# StairLightController.net
KiCad netlist of a schematic drawn in EAGLE
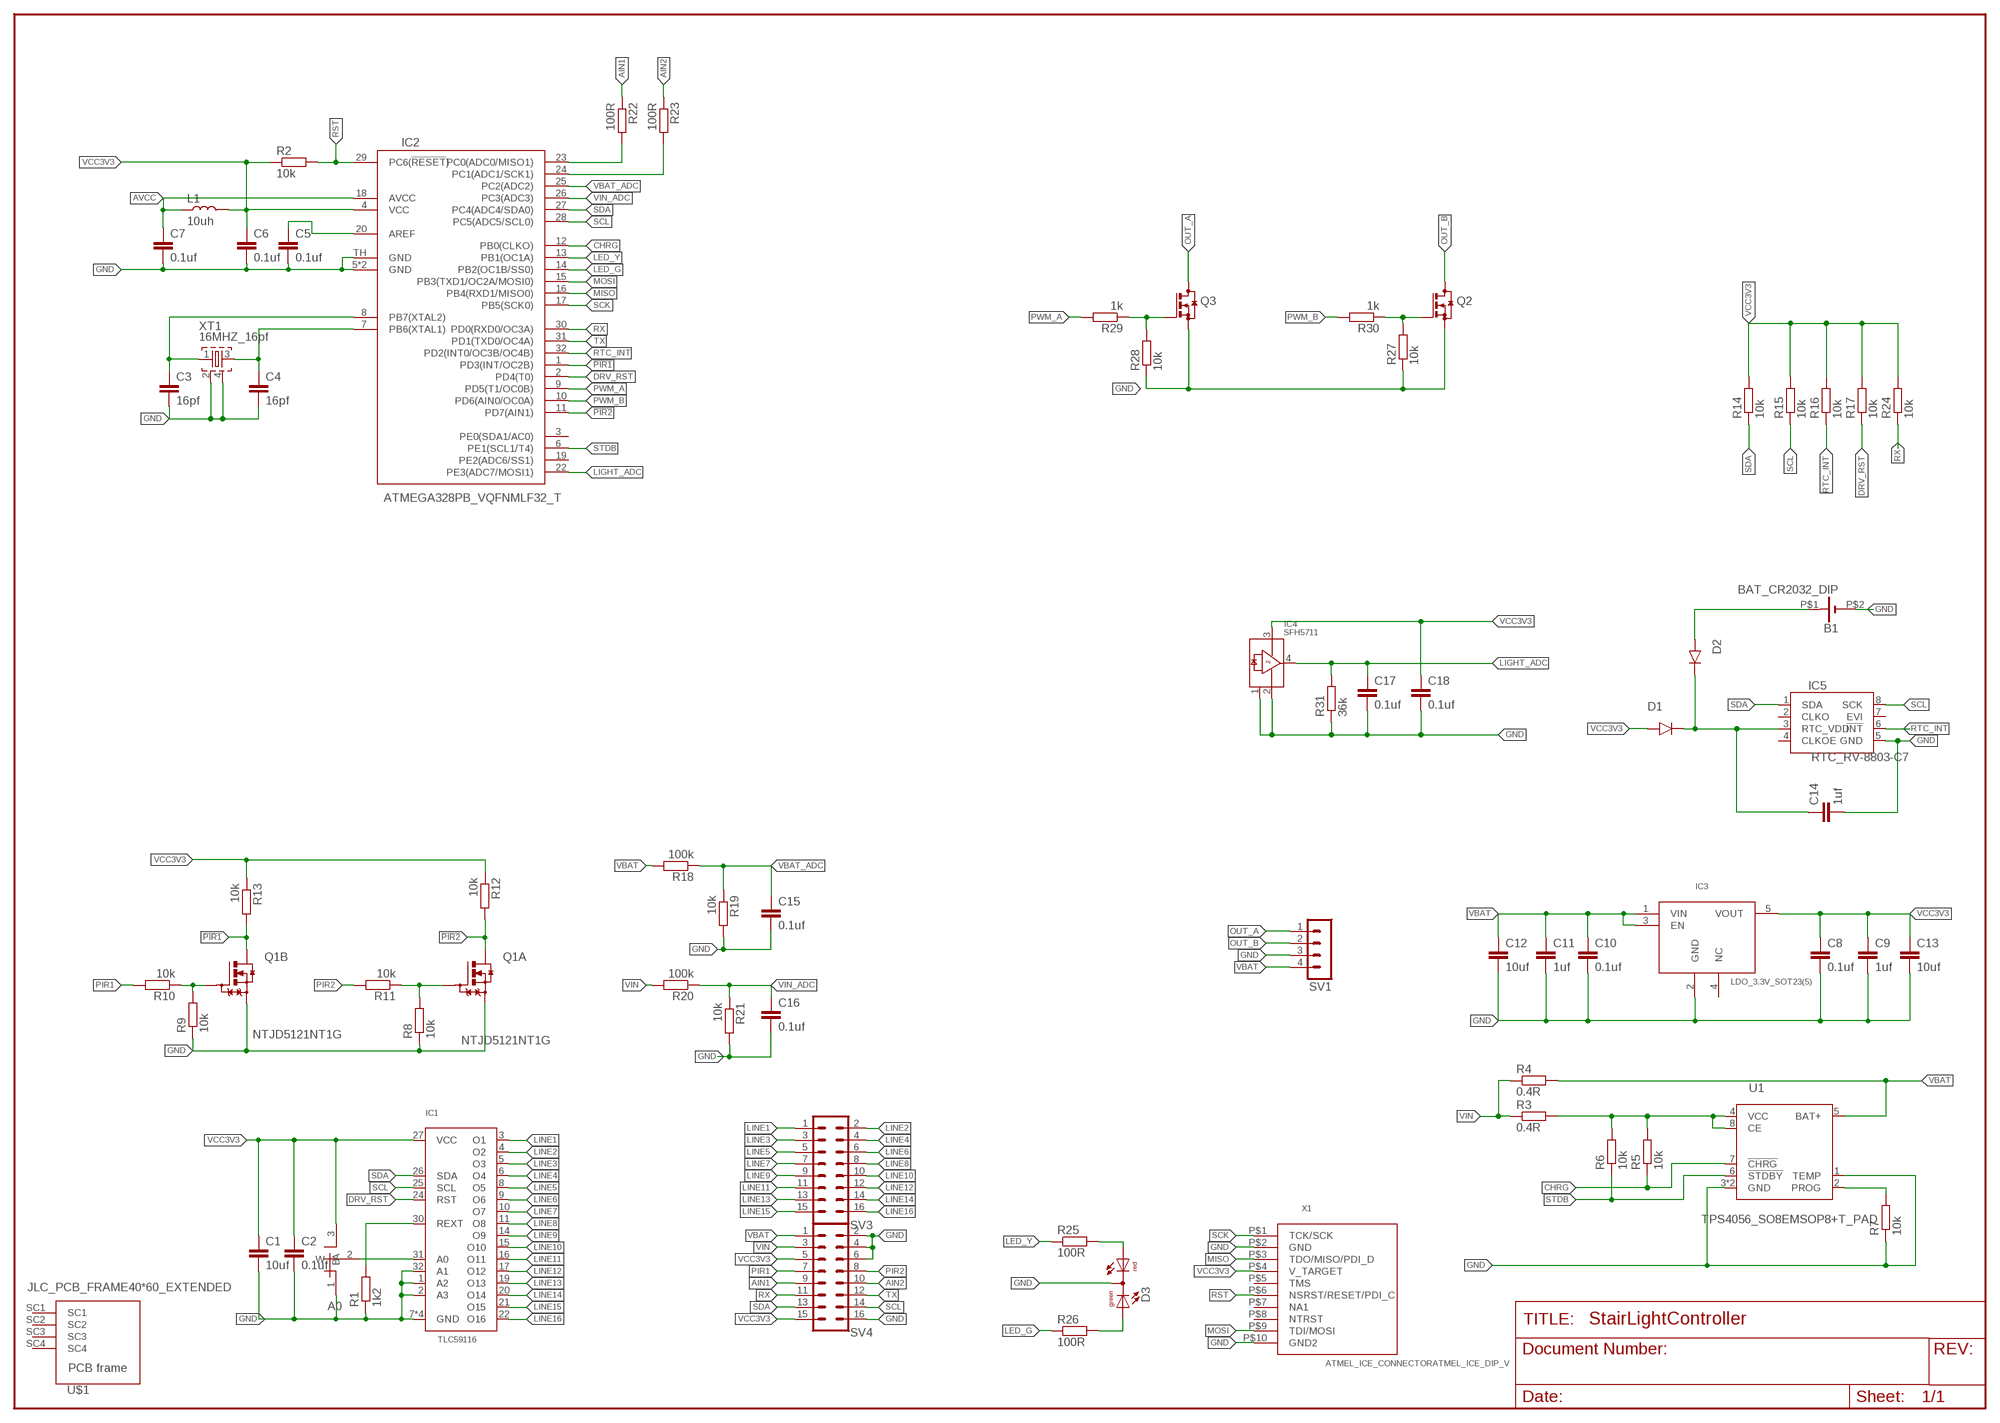
[diagram p0: schematic, sheet 1]

(export (version "E")
  (design (tool "Eeschema 10.0.6"))
  (components
    (comp (ref "A0")
      (value "SMD_SWITCH_JUMPER")
      (footprint "eagle-import:0603_JUMP")
      (libsource (lib "eagle-import") (part "SMD_SWITCH_JUMPER"))
    )
    (comp (ref "B1")
      (value "BAT_CR2032_DIP")
      (footprint "eagle-import:CR2032_DIP")
      (libsource (lib "eagle-import") (part "BAT_CR2032_DIP"))
    )
    (comp (ref "C1")
      (value "10uf")
      (footprint "eagle-import:0603")
      (libsource (lib "eagle-import") (part "SMD_C0603"))
    )
    (comp (ref "C2")
      (value "0.1uf")
      (footprint "eagle-import:0603")
      (libsource (lib "eagle-import") (part "SMD_C0603"))
    )
    (comp (ref "C3")
      (value "16pf")
      (footprint "eagle-import:0603")
      (libsource (lib "eagle-import") (part "SMD_C0603"))
    )
    (comp (ref "C4")
      (value "16pf")
      (footprint "eagle-import:0603")
      (libsource (lib "eagle-import") (part "SMD_C0603"))
    )
    (comp (ref "C5")
      (value "0.1uf")
      (footprint "eagle-import:0603")
      (libsource (lib "eagle-import") (part "SMD_C0603"))
    )
    (comp (ref "C6")
      (value "0.1uf")
      (footprint "eagle-import:0603")
      (libsource (lib "eagle-import") (part "SMD_C0603"))
    )
    (comp (ref "C7")
      (value "0.1uf")
      (footprint "eagle-import:0603")
      (libsource (lib "eagle-import") (part "SMD_C0603"))
    )
    (comp (ref "C8")
      (value "0.1uf")
      (footprint "eagle-import:0603")
      (libsource (lib "eagle-import") (part "SMD_C0603"))
    )
    (comp (ref "C9")
      (value "1uf")
      (footprint "eagle-import:0603")
      (libsource (lib "eagle-import") (part "SMD_C0603"))
    )
    (comp (ref "C10")
      (value "0.1uf")
      (footprint "eagle-import:0603")
      (libsource (lib "eagle-import") (part "SMD_C0603"))
    )
    (comp (ref "C11")
      (value "1uf")
      (footprint "eagle-import:0603")
      (libsource (lib "eagle-import") (part "SMD_C0603"))
    )
    (comp (ref "C12")
      (value "10uf")
      (footprint "eagle-import:1206")
      (libsource (lib "eagle-import") (part "SMD_C1206"))
    )
    (comp (ref "C13")
      (value "10uf")
      (footprint "eagle-import:1206")
      (libsource (lib "eagle-import") (part "SMD_C1206"))
    )
    (comp (ref "C14")
      (value "1uf")
      (footprint "eagle-import:0603")
      (libsource (lib "eagle-import") (part "SMD_C0603"))
    )
    (comp (ref "C15")
      (value "0.1uf")
      (footprint "eagle-import:0603")
      (libsource (lib "eagle-import") (part "SMD_C0603"))
    )
    (comp (ref "C16")
      (value "0.1uf")
      (footprint "eagle-import:0603")
      (libsource (lib "eagle-import") (part "SMD_C0603"))
    )
    (comp (ref "C17")
      (value "0.1uf")
      (footprint "eagle-import:0603")
      (libsource (lib "eagle-import") (part "SMD_C0603"))
    )
    (comp (ref "C18")
      (value "0.1uf")
      (footprint "eagle-import:0603")
      (libsource (lib "eagle-import") (part "SMD_C0603"))
    )
    (comp (ref "D1")
      (value "L1N4148WT1GSOD123_GALILE0_SMALL")
      (footprint "eagle-import:SOD-123_MINI-SMA")
      (libsource (lib "eagle-import") (part "L1N4148WT1GSOD123_GALILE0_SMALL"))
    )
    (comp (ref "D2")
      (value "L1N4148WT1GSOD123_GALILE0_SMALL")
      (footprint "eagle-import:SOD-123_MINI-SMA")
      (libsource (lib "eagle-import") (part "L1N4148WT1GSOD123_GALILE0_SMALL"))
    )
    (comp (ref "D3")
      (value "DUOLED5MM")
      (footprint "eagle-import:DUOLED5MM")
      (libsource (lib "eagle-import") (part "DUOLED5MM"))
    )
    (comp (ref "IC1")
      (value "TLC59116")
      (footprint "eagle-import:MLF32-TH")
      (libsource (lib "eagle-import") (part "TLC59116"))
    )
    (comp (ref "IC2")
      (value "ATMEGA328PB_VQFNMLF32_T")
      (footprint "eagle-import:MLF32-TH")
      (libsource (lib "eagle-import") (part "ATMEGA328PB_VQFNMLF32_T"))
    )
    (comp (ref "IC3")
      (value "LDO_3.3V_SOT23(5)")
      (footprint "eagle-import:SOT-23(5)")
      (libsource (lib "eagle-import") (part "LDO_3.3V_SOT23(5)"))
    )
    (comp (ref "IC4")
      (value "SFH5711")
      (footprint "eagle-import:SFH5711")
      (fields (field (name "MF") "OSRAM Opto"))
      (libsource (lib "eagle-import") (part "SFH5711"))
    )
    (comp (ref "IC5")
      (value "RTC_RV-8803-C7")
      (footprint "eagle-import:C7_RTC")
      (libsource (lib "eagle-import") (part "RTC_RV-8803-C7"))
    )
    (comp (ref "L1")
      (value "10uh")
      (footprint "eagle-import:0603")
      (libsource (lib "eagle-import") (part "SMD_L0603"))
    )
    (comp (ref "Q1")
      (value "NTJD5121NT1G")
      (footprint "eagle-import:SOT363")
      (fields (field (name "MF") "ON SEMICONDUCTOR"))
      (libsource (lib "eagle-import") (part "NTJD5121NT1G"))
    )
    (comp (ref "Q2")
      (value "BSS123SOT-23-3")
      (footprint "eagle-import:SOT-23(3)")
      (libsource (lib "eagle-import") (part "BSS123SOT-23-3"))
    )
    (comp (ref "Q3")
      (value "BSS123SOT-23-3")
      (footprint "eagle-import:SOT-23(3)")
      (libsource (lib "eagle-import") (part "BSS123SOT-23-3"))
    )
    (comp (ref "R1")
      (value "1k2")
      (footprint "eagle-import:0603")
      (libsource (lib "eagle-import") (part "SMD_R0603"))
    )
    (comp (ref "R2")
      (value "10k")
      (footprint "eagle-import:0603")
      (libsource (lib "eagle-import") (part "SMD_R0603"))
    )
    (comp (ref "R3")
      (value "0.4R")
      (footprint "eagle-import:1206")
      (libsource (lib "eagle-import") (part "SMD_R1206"))
    )
    (comp (ref "R4")
      (value "0.4R")
      (footprint "eagle-import:1206")
      (libsource (lib "eagle-import") (part "SMD_R1206"))
    )
    (comp (ref "R5")
      (value "10k")
      (footprint "eagle-import:0603")
      (libsource (lib "eagle-import") (part "SMD_R0603"))
    )
    (comp (ref "R6")
      (value "10k")
      (footprint "eagle-import:0603")
      (libsource (lib "eagle-import") (part "SMD_R0603"))
    )
    (comp (ref "R7")
      (value "10k")
      (footprint "eagle-import:0603")
      (libsource (lib "eagle-import") (part "SMD_R0603"))
    )
    (comp (ref "R8")
      (value "10k")
      (footprint "eagle-import:0603")
      (libsource (lib "eagle-import") (part "SMD_R0603"))
    )
    (comp (ref "R9")
      (value "10k")
      (footprint "eagle-import:0603")
      (libsource (lib "eagle-import") (part "SMD_R0603"))
    )
    (comp (ref "R10")
      (value "10k")
      (footprint "eagle-import:0603")
      (libsource (lib "eagle-import") (part "SMD_R0603"))
    )
    (comp (ref "R11")
      (value "10k")
      (footprint "eagle-import:0603")
      (libsource (lib "eagle-import") (part "SMD_R0603"))
    )
    (comp (ref "R12")
      (value "10k")
      (footprint "eagle-import:0603")
      (libsource (lib "eagle-import") (part "SMD_R0603"))
    )
    (comp (ref "R13")
      (value "10k")
      (footprint "eagle-import:0603")
      (libsource (lib "eagle-import") (part "SMD_R0603"))
    )
    (comp (ref "R14")
      (value "10k")
      (footprint "eagle-import:0603")
      (libsource (lib "eagle-import") (part "SMD_R0603"))
    )
    (comp (ref "R15")
      (value "10k")
      (footprint "eagle-import:0603")
      (libsource (lib "eagle-import") (part "SMD_R0603"))
    )
    (comp (ref "R16")
      (value "10k")
      (footprint "eagle-import:0603")
      (libsource (lib "eagle-import") (part "SMD_R0603"))
    )
    (comp (ref "R17")
      (value "10k")
      (footprint "eagle-import:0603")
      (libsource (lib "eagle-import") (part "SMD_R0603"))
    )
    (comp (ref "R18")
      (value "100k")
      (footprint "eagle-import:0603")
      (libsource (lib "eagle-import") (part "SMD_R0603"))
    )
    (comp (ref "R19")
      (value "10k")
      (footprint "eagle-import:0603")
      (libsource (lib "eagle-import") (part "SMD_R0603"))
    )
    (comp (ref "R20")
      (value "100k")
      (footprint "eagle-import:0603")
      (libsource (lib "eagle-import") (part "SMD_R0603"))
    )
    (comp (ref "R21")
      (value "10k")
      (footprint "eagle-import:0603")
      (libsource (lib "eagle-import") (part "SMD_R0603"))
    )
    (comp (ref "R22")
      (value "100R")
      (footprint "eagle-import:0603")
      (libsource (lib "eagle-import") (part "SMD_R0603"))
    )
    (comp (ref "R23")
      (value "100R")
      (footprint "eagle-import:0603")
      (libsource (lib "eagle-import") (part "SMD_R0603"))
    )
    (comp (ref "R24")
      (value "10k")
      (footprint "eagle-import:0603")
      (libsource (lib "eagle-import") (part "SMD_R0603"))
    )
    (comp (ref "R25")
      (value "100R")
      (footprint "eagle-import:0603")
      (libsource (lib "eagle-import") (part "SMD_R0603"))
    )
    (comp (ref "R26")
      (value "100R")
      (footprint "eagle-import:0603")
      (libsource (lib "eagle-import") (part "SMD_R0603"))
    )
    (comp (ref "R27")
      (value "10k")
      (footprint "eagle-import:0603")
      (libsource (lib "eagle-import") (part "SMD_R0603"))
    )
    (comp (ref "R28")
      (value "10k")
      (footprint "eagle-import:0603")
      (libsource (lib "eagle-import") (part "SMD_R0603"))
    )
    (comp (ref "R29")
      (value "1k")
      (footprint "eagle-import:0603")
      (libsource (lib "eagle-import") (part "SMD_R0603"))
    )
    (comp (ref "R30")
      (value "1k")
      (footprint "eagle-import:0603")
      (libsource (lib "eagle-import") (part "SMD_R0603"))
    )
    (comp (ref "R31")
      (value "36k")
      (footprint "eagle-import:0603")
      (libsource (lib "eagle-import") (part "SMD_R0603"))
    )
    (comp (ref "SV1")
      (value "MA04-1")
      (footprint "eagle-import:MA04-1")
      (libsource (lib "eagle-import") (part "MA04-1"))
    )
    (comp (ref "SV3")
      (value "MA08-2")
      (footprint "eagle-import:MA08-2")
      (libsource (lib "eagle-import") (part "MA08-2"))
    )
    (comp (ref "SV4")
      (value "MA08-2")
      (footprint "eagle-import:MA08-2")
      (libsource (lib "eagle-import") (part "MA08-2"))
    )
    (comp (ref "U$1")
      (value "JLC_PCB_FRAME40*60_EXTENDED")
      (footprint "eagle-import:40X60_SENSOR_UNIT_OPEN")
      (libsource (lib "eagle-import") (part "JLC_PCB_FRAME4060_EXTENDED"))
    )
    (comp (ref "U1")
      (value "TPS4056_SO8EMSOP8+T_PAD")
      (footprint "eagle-import:EMSOP8+TPAD")
      (libsource (lib "eagle-import") (part "TPS4056_SO8EMSOP8+T_PAD"))
    )
    (comp (ref "X1")
      (value "ATMEL_ICE_CONNECTORATMEL_ICE_DIP_V")
      (footprint "eagle-import:MINI10P_SPI_JTAG_PDI_DIP_V")
      (libsource (lib "eagle-import") (part "ATMEL_ICE_CONNECTORATMEL_ICE_DIP_V"))
    )
    (comp (ref "XT1")
      (value "16MHZ_16pf")
      (footprint "eagle-import:QUARTZ_3X3MM")
      (libsource (lib "eagle-import") (part "QUARTZ_ZQ"))
    )
  )
  (nets
    (net (code "1") (name "/~{PIR1}") (class "Default")
      (node (ref "IC2") (pin "1") (pinfunction "PD3(INT/OC2B)_1") (pintype "bidirectional"))
      (node (ref "Q1") (pin "3") (pinfunction "D_3") (pintype "passive"))
      (node (ref "R13") (pin "2") (pinfunction "2_2") (pintype "passive"))
    )
    (net (code "2") (name "/~{PIR2}") (class "Default")
      (node (ref "IC2") (pin "11") (pinfunction "PD7(AIN1)_11") (pintype "bidirectional"))
      (node (ref "Q1") (pin "6") (pinfunction "D_6") (pintype "passive"))
      (node (ref "R12") (pin "2") (pinfunction "2_2") (pintype "passive"))
    )
    (net (code "3") (name "AIN1") (class "Default")
      (node (ref "R22") (pin "1") (pinfunction "1_1") (pintype "passive"))
      (node (ref "SV4") (pin "9") (pinfunction "9_9") (pintype "passive"))
    )
    (net (code "4") (name "AIN2") (class "Default")
      (node (ref "R23") (pin "1") (pinfunction "1_1") (pintype "passive"))
      (node (ref "SV4") (pin "10") (pinfunction "10_10") (pintype "passive"))
    )
    (net (code "5") (name "AVCC") (class "Default")
      (node (ref "C7") (pin "1") (pinfunction "1_1") (pintype "passive"))
      (node (ref "IC2") (pin "18") (pinfunction "AVCC_18") (pintype "power_in"))
      (node (ref "L1") (pin "1") (pinfunction "1_1") (pintype "passive"))
    )
    (net (code "6") (name "CHRG") (class "Default")
      (node (ref "IC2") (pin "12") (pinfunction "PB0(CLKO)_12") (pintype "bidirectional"))
      (node (ref "R5") (pin "1") (pinfunction "1_1") (pintype "passive"))
      (node (ref "U1") (pin "7") (pinfunction "~{CHRG}_7") (pintype "bidirectional"))
    )
    (net (code "7") (name "DRV_RST") (class "Default")
      (node (ref "IC1") (pin "24") (pinfunction "RST_24") (pintype "bidirectional"))
      (node (ref "IC2") (pin "2") (pinfunction "PD4(T0)_2") (pintype "bidirectional"))
      (node (ref "R17") (pin "1") (pinfunction "1_1") (pintype "passive"))
    )
    (net (code "8") (name "GND") (class "Default")
      (node (ref "A0") (pin "1") (pinfunction "A_1") (pintype "bidirectional"))
      (node (ref "B1") (pin "P$2") (pinfunction "-_P$2") (pintype "passive"))
      (node (ref "C1") (pin "2") (pinfunction "2_2") (pintype "passive"))
      (node (ref "C10") (pin "2") (pinfunction "2_2") (pintype "passive"))
      (node (ref "C11") (pin "2") (pinfunction "2_2") (pintype "passive"))
      (node (ref "C12") (pin "2") (pinfunction "2_2") (pintype "passive"))
      (node (ref "C13") (pin "2") (pinfunction "2_2") (pintype "passive"))
      (node (ref "C14") (pin "2") (pinfunction "2_2") (pintype "passive"))
      (node (ref "C15") (pin "2") (pinfunction "2_2") (pintype "passive"))
      (node (ref "C16") (pin "2") (pinfunction "2_2") (pintype "passive"))
      (node (ref "C17") (pin "2") (pinfunction "2_2") (pintype "passive"))
      (node (ref "C18") (pin "2") (pinfunction "2_2") (pintype "passive"))
      (node (ref "C2") (pin "2") (pinfunction "2_2") (pintype "passive"))
      (node (ref "C3") (pin "2") (pinfunction "2_2") (pintype "passive"))
      (node (ref "C4") (pin "2") (pinfunction "2_2") (pintype "passive"))
      (node (ref "C5") (pin "2") (pinfunction "2_2") (pintype "passive"))
      (node (ref "C6") (pin "2") (pinfunction "2_2") (pintype "passive"))
      (node (ref "C7") (pin "2") (pinfunction "2_2") (pintype "passive"))
      (node (ref "C8") (pin "2") (pinfunction "2_2") (pintype "passive"))
      (node (ref "C9") (pin "2") (pinfunction "2_2") (pintype "passive"))
      (node (ref "D3") (pin "K") (pinfunction "C_K") (pintype "passive"))
      (node (ref "IC1") (pin "1") (pinfunction "A2_1") (pintype "bidirectional"))
      (node (ref "IC1") (pin "18") (pinfunction "GND_18") (pintype "bidirectional"))
      (node (ref "IC1") (pin "2") (pinfunction "A3_2") (pintype "bidirectional"))
      (node (ref "IC1") (pin "23") (pinfunction "GND_23") (pintype "bidirectional"))
      (node (ref "IC1") (pin "32") (pinfunction "A1_32") (pintype "bidirectional"))
      (node (ref "IC1") (pin "7") (pinfunction "GND_7") (pintype "bidirectional"))
      (node (ref "IC1") (pin "TH") (pinfunction "GND_TH") (pintype "bidirectional"))
      (node (ref "IC2") (pin "21") (pinfunction "GND_21") (pintype "power_in"))
      (node (ref "IC2") (pin "5") (pinfunction "GND_5") (pintype "power_in"))
      (node (ref "IC2") (pin "TH") (pinfunction "GND_TH") (pintype "power_in"))
      (node (ref "IC3") (pin "2") (pinfunction "GND_2") (pintype "bidirectional"))
      (node (ref "IC4") (pin "1") (pinfunction "1_1") (pintype "bidirectional"))
      (node (ref "IC4") (pin "2") (pinfunction "2_2") (pintype "bidirectional"))
      (node (ref "IC5") (pin "5") (pinfunction "GND_5") (pintype "bidirectional"))
      (node (ref "Q1") (pin "1") (pinfunction "S_1") (pintype "passive"))
      (node (ref "Q1") (pin "4") (pinfunction "S_4") (pintype "passive"))
      (node (ref "Q2") (pin "2") (pinfunction "S_2") (pintype "passive"))
      (node (ref "Q3") (pin "2") (pinfunction "S_2") (pintype "passive"))
      (node (ref "R1") (pin "1") (pinfunction "1_1") (pintype "passive"))
      (node (ref "R19") (pin "2") (pinfunction "2_2") (pintype "passive"))
      (node (ref "R21") (pin "2") (pinfunction "2_2") (pintype "passive"))
      (node (ref "R27") (pin "1") (pinfunction "1_1") (pintype "passive"))
      (node (ref "R28") (pin "1") (pinfunction "1_1") (pintype "passive"))
      (node (ref "R31") (pin "1") (pinfunction "1_1") (pintype "passive"))
      (node (ref "R7") (pin "1") (pinfunction "1_1") (pintype "passive"))
      (node (ref "R8") (pin "1") (pinfunction "1_1") (pintype "passive"))
      (node (ref "R9") (pin "1") (pinfunction "1_1") (pintype "passive"))
      (node (ref "SV1") (pin "3") (pinfunction "3_3") (pintype "passive"))
      (node (ref "SV4") (pin "16") (pinfunction "16_16") (pintype "passive"))
      (node (ref "SV4") (pin "2") (pinfunction "2_2") (pintype "passive"))
      (node (ref "SV4") (pin "4") (pinfunction "4_4") (pintype "passive"))
      (node (ref "SV4") (pin "6") (pinfunction "6_6") (pintype "passive"))
      (node (ref "U1") (pin "1") (pinfunction "TEMP_1") (pintype "bidirectional"))
      (node (ref "U1") (pin "3") (pinfunction "GND_3") (pintype "bidirectional"))
      (node (ref "U1") (pin "TPAD") (pinfunction "GND_TPAD") (pintype "bidirectional"))
      (node (ref "X1") (pin "P$10") (pinfunction "GND2_P$10") (pintype "bidirectional"))
      (node (ref "X1") (pin "P$2") (pinfunction "GND_P$2") (pintype "bidirectional"))
      (node (ref "XT1") (pin "2") (pinfunction "2_2") (pintype "passive"))
      (node (ref "XT1") (pin "4") (pinfunction "4_4") (pintype "passive"))
    )
    (net (code "9") (name "LED_G") (class "Default")
      (node (ref "IC2") (pin "14") (pinfunction "PB2(OC1B/SS0)_14") (pintype "bidirectional"))
      (node (ref "R26") (pin "1") (pinfunction "1_1") (pintype "passive"))
    )
    (net (code "10") (name "LED_Y") (class "Default")
      (node (ref "IC2") (pin "13") (pinfunction "PB1(OC1A)_13") (pintype "bidirectional"))
      (node (ref "R25") (pin "1") (pinfunction "1_1") (pintype "passive"))
    )
    (net (code "11") (name "LIGHT_ADC") (class "Default")
      (node (ref "C17") (pin "1") (pinfunction "1_1") (pintype "passive"))
      (node (ref "IC2") (pin "22") (pinfunction "PE3(ADC7/MOSI1)_22") (pintype "bidirectional"))
      (node (ref "IC4") (pin "4") (pinfunction "4_4") (pintype "bidirectional"))
      (node (ref "R31") (pin "2") (pinfunction "2_2") (pintype "passive"))
    )
    (net (code "12") (name "LINE1") (class "Default")
      (node (ref "IC1") (pin "3") (pinfunction "O1_3") (pintype "bidirectional"))
      (node (ref "SV3") (pin "1") (pinfunction "1_1") (pintype "passive"))
    )
    (net (code "13") (name "LINE2") (class "Default")
      (node (ref "IC1") (pin "4") (pinfunction "O2_4") (pintype "bidirectional"))
      (node (ref "SV3") (pin "2") (pinfunction "2_2") (pintype "passive"))
    )
    (net (code "14") (name "LINE3") (class "Default")
      (node (ref "IC1") (pin "5") (pinfunction "O3_5") (pintype "bidirectional"))
      (node (ref "SV3") (pin "3") (pinfunction "3_3") (pintype "passive"))
    )
    (net (code "15") (name "LINE4") (class "Default")
      (node (ref "IC1") (pin "6") (pinfunction "O4_6") (pintype "bidirectional"))
      (node (ref "SV3") (pin "4") (pinfunction "4_4") (pintype "passive"))
    )
    (net (code "16") (name "LINE5") (class "Default")
      (node (ref "IC1") (pin "8") (pinfunction "O5_8") (pintype "bidirectional"))
      (node (ref "SV3") (pin "5") (pinfunction "5_5") (pintype "passive"))
    )
    (net (code "17") (name "LINE6") (class "Default")
      (node (ref "IC1") (pin "9") (pinfunction "O6_9") (pintype "bidirectional"))
      (node (ref "SV3") (pin "6") (pinfunction "6_6") (pintype "passive"))
    )
    (net (code "18") (name "LINE7") (class "Default")
      (node (ref "IC1") (pin "10") (pinfunction "O7_10") (pintype "bidirectional"))
      (node (ref "SV3") (pin "7") (pinfunction "7_7") (pintype "passive"))
    )
    (net (code "19") (name "LINE8") (class "Default")
      (node (ref "IC1") (pin "11") (pinfunction "O8_11") (pintype "bidirectional"))
      (node (ref "SV3") (pin "8") (pinfunction "8_8") (pintype "passive"))
    )
    (net (code "20") (name "LINE9") (class "Default")
      (node (ref "IC1") (pin "14") (pinfunction "O9_14") (pintype "bidirectional"))
      (node (ref "SV3") (pin "9") (pinfunction "9_9") (pintype "passive"))
    )
    (net (code "21") (name "LINE10") (class "Default")
      (node (ref "IC1") (pin "15") (pinfunction "O10_15") (pintype "bidirectional"))
      (node (ref "SV3") (pin "10") (pinfunction "10_10") (pintype "passive"))
    )
    (net (code "22") (name "LINE11") (class "Default")
      (node (ref "IC1") (pin "16") (pinfunction "O11_16") (pintype "bidirectional"))
      (node (ref "SV3") (pin "11") (pinfunction "11_11") (pintype "passive"))
    )
    (net (code "23") (name "LINE12") (class "Default")
      (node (ref "IC1") (pin "17") (pinfunction "O12_17") (pintype "bidirectional"))
      (node (ref "SV3") (pin "12") (pinfunction "12_12") (pintype "passive"))
    )
    (net (code "24") (name "LINE13") (class "Default")
      (node (ref "IC1") (pin "19") (pinfunction "O13_19") (pintype "bidirectional"))
      (node (ref "SV3") (pin "13") (pinfunction "13_13") (pintype "passive"))
    )
    (net (code "25") (name "LINE14") (class "Default")
      (node (ref "IC1") (pin "20") (pinfunction "O14_20") (pintype "bidirectional"))
      (node (ref "SV3") (pin "14") (pinfunction "14_14") (pintype "passive"))
    )
    (net (code "26") (name "LINE15") (class "Default")
      (node (ref "IC1") (pin "21") (pinfunction "O15_21") (pintype "bidirectional"))
      (node (ref "SV3") (pin "15") (pinfunction "15_15") (pintype "passive"))
    )
    (net (code "27") (name "LINE16") (class "Default")
      (node (ref "IC1") (pin "22") (pinfunction "O16_22") (pintype "bidirectional"))
      (node (ref "SV3") (pin "16") (pinfunction "16_16") (pintype "passive"))
    )
    (net (code "28") (name "MISO") (class "Default")
      (node (ref "IC2") (pin "16") (pinfunction "PB4(RXD1/MISO0)_16") (pintype "bidirectional"))
      (node (ref "X1") (pin "P$3") (pinfunction "TDO/MISO/PDI_D_P$3") (pintype "bidirectional"))
    )
    (net (code "29") (name "MOSI") (class "Default")
      (node (ref "IC2") (pin "15") (pinfunction "PB3(TXD1/OC2A/MOSI0)_15") (pintype "bidirectional"))
      (node (ref "X1") (pin "P$9") (pinfunction "TDI/MOSI_P$9") (pintype "bidirectional"))
    )
    (net (code "30") (name "Net-(A0-W)") (class "Default")
      (node (ref "A0") (pin "2") (pinfunction "W_2") (pintype "bidirectional"))
      (node (ref "IC1") (pin "31") (pinfunction "A0_31") (pintype "bidirectional"))
    )
    (net (code "31") (name "Net-(B1-+)") (class "Default")
      (node (ref "B1") (pin "P$1") (pinfunction "+_P$1") (pintype "passive"))
      (node (ref "D2") (pin "A") (pinfunction "A_A") (pintype "bidirectional"))
    )
    (net (code "32") (name "Net-(D3-PadAG)") (class "Default")
      (node (ref "D3") (pin "AG") (pinfunction "AG_AG") (pintype "passive"))
      (node (ref "R26") (pin "2") (pinfunction "2_2") (pintype "passive"))
    )
    (net (code "33") (name "Net-(D3-PadAR)") (class "Default")
      (node (ref "D3") (pin "AR") (pinfunction "AR_AR") (pintype "passive"))
      (node (ref "R25") (pin "2") (pinfunction "2_2") (pintype "passive"))
    )
    (net (code "34") (name "Net-(IC1-REXT)") (class "Default")
      (node (ref "IC1") (pin "30") (pinfunction "REXT_30") (pintype "bidirectional"))
      (node (ref "R1") (pin "2") (pinfunction "2_2") (pintype "passive"))
    )
    (net (code "35") (name "Net-(IC2-AREF)") (class "Default")
      (node (ref "C5") (pin "1") (pinfunction "1_1") (pintype "passive"))
      (node (ref "IC2") (pin "20") (pinfunction "AREF_20") (pintype "passive"))
    )
    (net (code "36") (name "Net-(IC2-PB6(XTAL1))") (class "Default")
      (node (ref "C4") (pin "1") (pinfunction "1_1") (pintype "passive"))
      (node (ref "IC2") (pin "7") (pinfunction "PB6(XTAL1)_7") (pintype "bidirectional"))
      (node (ref "XT1") (pin "3") (pinfunction "3_3") (pintype "passive"))
    )
    (net (code "37") (name "Net-(IC2-PB7(XTAL2))") (class "Default")
      (node (ref "C3") (pin "1") (pinfunction "1_1") (pintype "passive"))
      (node (ref "IC2") (pin "8") (pinfunction "PB7(XTAL2)_8") (pintype "bidirectional"))
      (node (ref "XT1") (pin "1") (pinfunction "1_1") (pintype "passive"))
    )
    (net (code "38") (name "Net-(IC2-PC0(ADC0{slash}MISO1))") (class "Default")
      (node (ref "IC2") (pin "23") (pinfunction "PC0(ADC0/MISO1)_23") (pintype "bidirectional"))
      (node (ref "R22") (pin "2") (pinfunction "2_2") (pintype "passive"))
    )
    (net (code "39") (name "Net-(IC2-PC1(ADC1{slash}SCK1))") (class "Default")
      (node (ref "IC2") (pin "24") (pinfunction "PC1(ADC1/SCK1)_24") (pintype "bidirectional"))
      (node (ref "R23") (pin "2") (pinfunction "2_2") (pintype "passive"))
    )
    (net (code "40") (name "Net-(IC5-RTC_VDD)") (class "Default")
      (node (ref "C14") (pin "1") (pinfunction "1_1") (pintype "passive"))
      (node (ref "D1") (pin "C") (pinfunction "C_C") (pintype "bidirectional"))
      (node (ref "D2") (pin "C") (pinfunction "C_C") (pintype "bidirectional"))
      (node (ref "IC5") (pin "3") (pinfunction "RTC_VDD_3") (pintype "bidirectional"))
    )
    (net (code "41") (name "Net-(Q1A-G)") (class "Default")
      (node (ref "Q1") (pin "2") (pinfunction "G_2") (pintype "passive"))
      (node (ref "R11") (pin "1") (pinfunction "1_1") (pintype "passive"))
      (node (ref "R8") (pin "2") (pinfunction "2_2") (pintype "passive"))
    )
    (net (code "42") (name "Net-(Q1B-G)") (class "Default")
      (node (ref "Q1") (pin "5") (pinfunction "G_5") (pintype "passive"))
      (node (ref "R10") (pin "1") (pinfunction "1_1") (pintype "passive"))
      (node (ref "R9") (pin "2") (pinfunction "2_2") (pintype "passive"))
    )
    (net (code "43") (name "Net-(Q2-G)") (class "Default")
      (node (ref "Q2") (pin "1") (pinfunction "G_1") (pintype "passive"))
      (node (ref "R27") (pin "2") (pinfunction "2_2") (pintype "passive"))
      (node (ref "R30") (pin "1") (pinfunction "1_1") (pintype "passive"))
    )
    (net (code "44") (name "Net-(Q3-G)") (class "Default")
      (node (ref "Q3") (pin "1") (pinfunction "G_1") (pintype "passive"))
      (node (ref "R28") (pin "2") (pinfunction "2_2") (pintype "passive"))
      (node (ref "R29") (pin "1") (pinfunction "1_1") (pintype "passive"))
    )
    (net (code "45") (name "Net-(U1-CE)") (class "Default")
      (node (ref "R3") (pin "2") (pinfunction "2_2") (pintype "passive"))
      (node (ref "R5") (pin "2") (pinfunction "2_2") (pintype "passive"))
      (node (ref "R6") (pin "2") (pinfunction "2_2") (pintype "passive"))
      (node (ref "U1") (pin "4") (pinfunction "VCC_4") (pintype "bidirectional"))
      (node (ref "U1") (pin "8") (pinfunction "CE_8") (pintype "bidirectional"))
    )
    (net (code "46") (name "Net-(U1-PROG)") (class "Default")
      (node (ref "R7") (pin "2") (pinfunction "2_2") (pintype "passive"))
      (node (ref "U1") (pin "2") (pinfunction "PROG_2") (pintype "bidirectional"))
    )
    (net (code "47") (name "OUT_A") (class "Default")
      (node (ref "Q3") (pin "3") (pinfunction "D_3") (pintype "passive"))
      (node (ref "SV1") (pin "1") (pinfunction "1_1") (pintype "passive"))
    )
    (net (code "48") (name "OUT_B") (class "Default")
      (node (ref "Q2") (pin "3") (pinfunction "D_3") (pintype "passive"))
      (node (ref "SV1") (pin "2") (pinfunction "2_2") (pintype "passive"))
    )
    (net (code "49") (name "PIR1") (class "Default")
      (node (ref "R10") (pin "2") (pinfunction "2_2") (pintype "passive"))
      (node (ref "SV4") (pin "7") (pinfunction "7_7") (pintype "passive"))
    )
    (net (code "50") (name "PIR2") (class "Default")
      (node (ref "R11") (pin "2") (pinfunction "2_2") (pintype "passive"))
      (node (ref "SV4") (pin "8") (pinfunction "8_8") (pintype "passive"))
    )
    (net (code "51") (name "PWM_A") (class "Default")
      (node (ref "IC2") (pin "9") (pinfunction "PD5(T1/OC0B)_9") (pintype "bidirectional"))
      (node (ref "R29") (pin "2") (pinfunction "2_2") (pintype "passive"))
    )
    (net (code "52") (name "PWM_B") (class "Default")
      (node (ref "IC2") (pin "10") (pinfunction "PD6(AIN0/OC0A)_10") (pintype "bidirectional"))
      (node (ref "R30") (pin "2") (pinfunction "2_2") (pintype "passive"))
    )
    (net (code "53") (name "RST") (class "Default")
      (node (ref "IC2") (pin "29") (pinfunction "PC6(~{RESET})_29") (pintype "bidirectional"))
      (node (ref "R2") (pin "2") (pinfunction "2_2") (pintype "passive"))
      (node (ref "X1") (pin "P$6") (pinfunction "NSRST/RESET/PDI_C_P$6") (pintype "bidirectional"))
    )
    (net (code "54") (name "RTC_INT") (class "Default")
      (node (ref "IC2") (pin "32") (pinfunction "PD2(INT0/OC3B/OC4B)_32") (pintype "bidirectional"))
      (node (ref "IC5") (pin "6") (pinfunction "~{INT}_6") (pintype "bidirectional"))
      (node (ref "R16") (pin "1") (pinfunction "1_1") (pintype "passive"))
    )
    (net (code "55") (name "RX") (class "Default")
      (node (ref "IC2") (pin "30") (pinfunction "PD0(RXD0/OC3A)_30") (pintype "bidirectional"))
      (node (ref "R24") (pin "1") (pinfunction "1_1") (pintype "passive"))
      (node (ref "SV4") (pin "11") (pinfunction "11_11") (pintype "passive"))
    )
    (net (code "56") (name "SCK") (class "Default")
      (node (ref "IC2") (pin "17") (pinfunction "PB5(SCK0)_17") (pintype "bidirectional"))
      (node (ref "X1") (pin "P$1") (pinfunction "TCK/SCK_P$1") (pintype "bidirectional"))
    )
    (net (code "57") (name "SCL") (class "Default")
      (node (ref "IC1") (pin "25") (pinfunction "SCL_25") (pintype "bidirectional"))
      (node (ref "IC2") (pin "28") (pinfunction "PC5(ADC5/SCL0)_28") (pintype "bidirectional"))
      (node (ref "IC5") (pin "8") (pinfunction "SCK_8") (pintype "bidirectional"))
      (node (ref "R15") (pin "1") (pinfunction "1_1") (pintype "passive"))
      (node (ref "SV4") (pin "14") (pinfunction "14_14") (pintype "passive"))
    )
    (net (code "58") (name "SDA") (class "Default")
      (node (ref "IC1") (pin "26") (pinfunction "SDA_26") (pintype "bidirectional"))
      (node (ref "IC2") (pin "27") (pinfunction "PC4(ADC4/SDA0)_27") (pintype "bidirectional"))
      (node (ref "IC5") (pin "1") (pinfunction "SDA_1") (pintype "bidirectional"))
      (node (ref "R14") (pin "1") (pinfunction "1_1") (pintype "passive"))
      (node (ref "SV4") (pin "13") (pinfunction "13_13") (pintype "passive"))
    )
    (net (code "59") (name "STDB") (class "Default")
      (node (ref "IC2") (pin "6") (pinfunction "PE1(SCL1/T4)_6") (pintype "bidirectional"))
      (node (ref "R6") (pin "1") (pinfunction "1_1") (pintype "passive"))
      (node (ref "U1") (pin "6") (pinfunction "~{STDBY}_6") (pintype "bidirectional"))
    )
    (net (code "60") (name "TX") (class "Default")
      (node (ref "IC2") (pin "31") (pinfunction "PD1(TXD0/OC4A)_31") (pintype "bidirectional"))
      (node (ref "SV4") (pin "12") (pinfunction "12_12") (pintype "passive"))
    )
    (net (code "61") (name "VBAT") (class "Default")
      (node (ref "C10") (pin "1") (pinfunction "1_1") (pintype "passive"))
      (node (ref "C11") (pin "1") (pinfunction "1_1") (pintype "passive"))
      (node (ref "C12") (pin "1") (pinfunction "1_1") (pintype "passive"))
      (node (ref "IC3") (pin "1") (pinfunction "VIN_1") (pintype "bidirectional"))
      (node (ref "IC3") (pin "3") (pinfunction "EN_3") (pintype "bidirectional"))
      (node (ref "R18") (pin "2") (pinfunction "2_2") (pintype "passive"))
      (node (ref "R4") (pin "2") (pinfunction "2_2") (pintype "passive"))
      (node (ref "SV1") (pin "4") (pinfunction "4_4") (pintype "passive"))
      (node (ref "SV4") (pin "1") (pinfunction "1_1") (pintype "passive"))
      (node (ref "U1") (pin "5") (pinfunction "BAT+_5") (pintype "bidirectional"))
    )
    (net (code "62") (name "VBAT_ADC") (class "Default")
      (node (ref "C15") (pin "1") (pinfunction "1_1") (pintype "passive"))
      (node (ref "IC2") (pin "25") (pinfunction "PC2(ADC2)_25") (pintype "bidirectional"))
      (node (ref "R18") (pin "1") (pinfunction "1_1") (pintype "passive"))
      (node (ref "R19") (pin "1") (pinfunction "1_1") (pintype "passive"))
    )
    (net (code "63") (name "VCC3V3") (class "Default")
      (node (ref "A0") (pin "3") (pinfunction "B_3") (pintype "bidirectional"))
      (node (ref "C1") (pin "1") (pinfunction "1_1") (pintype "passive"))
      (node (ref "C13") (pin "1") (pinfunction "1_1") (pintype "passive"))
      (node (ref "C18") (pin "1") (pinfunction "1_1") (pintype "passive"))
      (node (ref "C2") (pin "1") (pinfunction "1_1") (pintype "passive"))
      (node (ref "C6") (pin "1") (pinfunction "1_1") (pintype "passive"))
      (node (ref "C8") (pin "1") (pinfunction "1_1") (pintype "passive"))
      (node (ref "C9") (pin "1") (pinfunction "1_1") (pintype "passive"))
      (node (ref "D1") (pin "A") (pinfunction "A_A") (pintype "bidirectional"))
      (node (ref "IC1") (pin "27") (pinfunction "VCC_27") (pintype "bidirectional"))
      (node (ref "IC2") (pin "4") (pinfunction "VCC_4") (pintype "power_in"))
      (node (ref "IC3") (pin "5") (pinfunction "VOUT_5") (pintype "bidirectional"))
      (node (ref "IC4") (pin "3") (pinfunction "3_3") (pintype "bidirectional"))
      (node (ref "L1") (pin "2") (pinfunction "2_2") (pintype "passive"))
      (node (ref "R12") (pin "1") (pinfunction "1_1") (pintype "passive"))
      (node (ref "R13") (pin "1") (pinfunction "1_1") (pintype "passive"))
      (node (ref "R14") (pin "2") (pinfunction "2_2") (pintype "passive"))
      (node (ref "R15") (pin "2") (pinfunction "2_2") (pintype "passive"))
      (node (ref "R16") (pin "2") (pinfunction "2_2") (pintype "passive"))
      (node (ref "R17") (pin "2") (pinfunction "2_2") (pintype "passive"))
      (node (ref "R2") (pin "1") (pinfunction "1_1") (pintype "passive"))
      (node (ref "R24") (pin "2") (pinfunction "2_2") (pintype "passive"))
      (node (ref "SV4") (pin "15") (pinfunction "15_15") (pintype "passive"))
      (node (ref "SV4") (pin "5") (pinfunction "5_5") (pintype "passive"))
      (node (ref "X1") (pin "P$4") (pinfunction "V_TARGET_P$4") (pintype "bidirectional"))
    )
    (net (code "64") (name "VIN") (class "Default")
      (node (ref "R20") (pin "2") (pinfunction "2_2") (pintype "passive"))
      (node (ref "R3") (pin "1") (pinfunction "1_1") (pintype "passive"))
      (node (ref "R4") (pin "1") (pinfunction "1_1") (pintype "passive"))
      (node (ref "SV4") (pin "3") (pinfunction "3_3") (pintype "passive"))
    )
    (net (code "65") (name "VIN_ADC") (class "Default")
      (node (ref "C16") (pin "1") (pinfunction "1_1") (pintype "passive"))
      (node (ref "IC2") (pin "26") (pinfunction "PC3(ADC3)_26") (pintype "bidirectional"))
      (node (ref "R20") (pin "1") (pinfunction "1_1") (pintype "passive"))
      (node (ref "R21") (pin "1") (pinfunction "1_1") (pintype "passive"))
    )
    (net (code "66") (name "unconnected-(IC2-PE0(SDA1{slash}AC0)-Pad3)") (class "Default")
      (node (ref "IC2") (pin "3") (pinfunction "PE0(SDA1/AC0)_3") (pintype "bidirectional"))
    )
    (net (code "67") (name "unconnected-(IC2-PE2(ADC6{slash}SS1)-Pad19)") (class "Default")
      (node (ref "IC2") (pin "19") (pinfunction "PE2(ADC6/SS1)_19") (pintype "bidirectional"))
    )
    (net (code "68") (name "unconnected-(IC3-NC-Pad4)") (class "Default")
      (node (ref "IC3") (pin "4") (pinfunction "NC_4") (pintype "bidirectional"))
    )
    (net (code "69") (name "unconnected-(IC5-CLKO-Pad2)") (class "Default")
      (node (ref "IC5") (pin "2") (pinfunction "CLKO_2") (pintype "bidirectional"))
    )
    (net (code "70") (name "unconnected-(IC5-CLKOE-Pad4)") (class "Default")
      (node (ref "IC5") (pin "4") (pinfunction "CLKOE_4") (pintype "bidirectional"))
    )
    (net (code "71") (name "unconnected-(IC5-EVI-Pad7)") (class "Default")
      (node (ref "IC5") (pin "7") (pinfunction "EVI_7") (pintype "bidirectional"))
    )
    (net (code "72") (name "unconnected-(U$1-PadSC1)") (class "Default")
      (node (ref "U$1") (pin "SC1") (pinfunction "SC1_SC1") (pintype "bidirectional"))
    )
    (net (code "73") (name "unconnected-(U$1-PadSC2)") (class "Default")
      (node (ref "U$1") (pin "SC2") (pinfunction "SC2_SC2") (pintype "bidirectional"))
    )
    (net (code "74") (name "unconnected-(U$1-PadSC3)") (class "Default")
      (node (ref "U$1") (pin "SC3") (pinfunction "SC3_SC3") (pintype "bidirectional"))
    )
    (net (code "75") (name "unconnected-(U$1-PadSC4)") (class "Default")
      (node (ref "U$1") (pin "SC4") (pinfunction "SC4_SC4") (pintype "bidirectional"))
    )
    (net (code "76") (name "unconnected-(X1-NA1-PadP$7)") (class "Default")
      (node (ref "X1") (pin "P$7") (pinfunction "NA1_P$7") (pintype "bidirectional"))
    )
    (net (code "77") (name "unconnected-(X1-NTRST-PadP$8)") (class "Default")
      (node (ref "X1") (pin "P$8") (pinfunction "NTRST_P$8") (pintype "bidirectional"))
    )
    (net (code "78") (name "unconnected-(X1-TMS-PadP$5)") (class "Default")
      (node (ref "X1") (pin "P$5") (pinfunction "TMS_P$5") (pintype "bidirectional"))
    )
  )
)
